# Serial_Card_V3.net
KiCad netlist of a schematic drawn in EAGLE
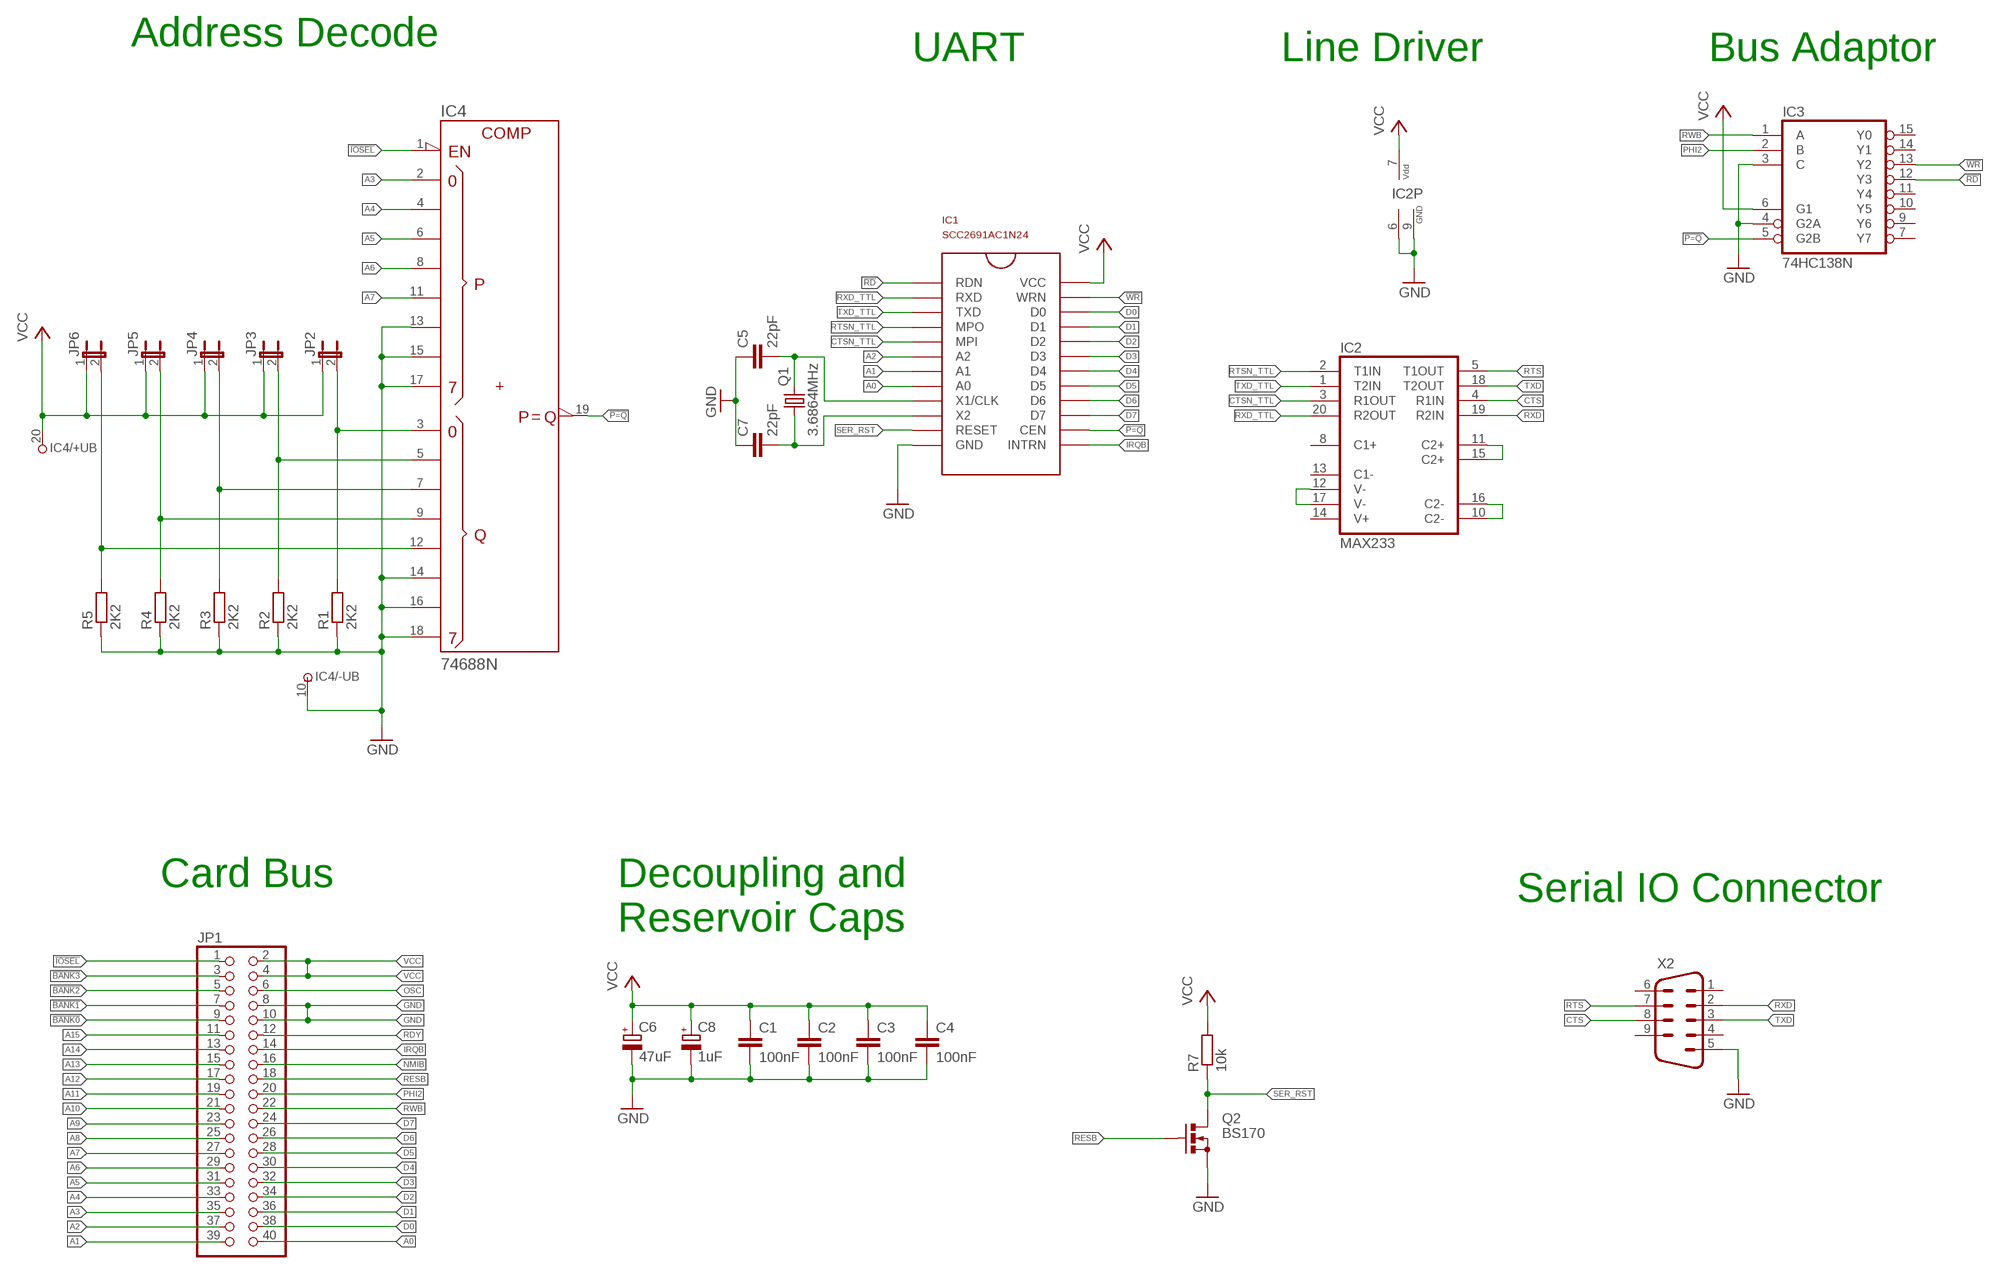
[diagram p0: schematic, sheet 1]

(export (version "E")
  (design (tool "Eeschema 10.0.6"))
  (components
    (comp (ref "C1")
      (value "100nF")
      (footprint "eagle-import:C050-025X075")
      (libsource (lib "eagle-import") (part "C-EU050-025X075"))
    )
    (comp (ref "C2")
      (value "100nF")
      (footprint "eagle-import:C050-025X075")
      (libsource (lib "eagle-import") (part "C-EU050-025X075"))
    )
    (comp (ref "C3")
      (value "100nF")
      (footprint "eagle-import:C050-025X075")
      (libsource (lib "eagle-import") (part "C-EU050-025X075"))
    )
    (comp (ref "C4")
      (value "100nF")
      (footprint "eagle-import:C050-025X075")
      (libsource (lib "eagle-import") (part "C-EU050-025X075"))
    )
    (comp (ref "C5")
      (value "22pF")
      (footprint "eagle-import:C025-024X044")
      (libsource (lib "eagle-import") (part "C-EU025-024X044"))
    )
    (comp (ref "C6")
      (value "47uF")
      (footprint "eagle-import:E2,5-7")
      (libsource (lib "eagle-import") (part "CPOL-EUE2.5-7"))
    )
    (comp (ref "C7")
      (value "22pF")
      (footprint "eagle-import:C025-024X044")
      (libsource (lib "eagle-import") (part "C-EU025-024X044"))
    )
    (comp (ref "C8")
      (value "1uF")
      (footprint "eagle-import:E5-5")
      (libsource (lib "eagle-import") (part "CPOL-EUE5-5"))
    )
    (comp (ref "IC1")
      (value "SCC2691AC1N24")
      (footprint "eagle-import:DIP")
      (libsource (lib "eagle-import") (part "SCC2691AC1N24"))
    )
    (comp (ref "IC2")
      (value "MAX233")
      (footprint "eagle-import:DIL20")
      (libsource (lib "eagle-import") (part "MAX233"))
    )
    (comp (ref "IC3")
      (value "74HC138N")
      (footprint "eagle-import:DIL16")
      (libsource (lib "eagle-import") (part "74138NHC"))
    )
    (comp (ref "IC4")
      (value "74688N")
      (footprint "eagle-import:DIL20")
      (libsource (lib "eagle-import") (part "74688N"))
    )
    (comp (ref "JP1")
      (value "PINHD-2X20/90")
      (footprint "eagle-import:2X20_90")
      (libsource (lib "eagle-import") (part "PINHD-2X20/90"))
    )
    (comp (ref "JP2")
      (value "JP1E")
      (footprint "eagle-import:JP1")
      (libsource (lib "eagle-import") (part "JP1E"))
    )
    (comp (ref "JP3")
      (value "JP1E")
      (footprint "eagle-import:JP1")
      (libsource (lib "eagle-import") (part "JP1E"))
    )
    (comp (ref "JP4")
      (value "JP1E")
      (footprint "eagle-import:JP1")
      (libsource (lib "eagle-import") (part "JP1E"))
    )
    (comp (ref "JP5")
      (value "JP1E")
      (footprint "eagle-import:JP1")
      (libsource (lib "eagle-import") (part "JP1E"))
    )
    (comp (ref "JP6")
      (value "JP1E")
      (footprint "eagle-import:JP1")
      (libsource (lib "eagle-import") (part "JP1E"))
    )
    (comp (ref "Q1")
      (value "3.6864MHz")
      (footprint "eagle-import:HC49_S")
      (libsource (lib "eagle-import") (part "CRYSTALHC49S"))
    )
    (comp (ref "Q2")
      (value "BS170")
      (footprint "eagle-import:SOT54E")
      (libsource (lib "eagle-import") (part "BS170"))
    )
    (comp (ref "R1")
      (value "2K2")
      (footprint "eagle-import:0207_2V")
      (libsource (lib "eagle-import") (part "R-EU_0207/2V"))
    )
    (comp (ref "R2")
      (value "2K2")
      (footprint "eagle-import:0207_2V")
      (libsource (lib "eagle-import") (part "R-EU_0207/2V"))
    )
    (comp (ref "R3")
      (value "2K2")
      (footprint "eagle-import:0207_2V")
      (libsource (lib "eagle-import") (part "R-EU_0207/2V"))
    )
    (comp (ref "R4")
      (value "2K2")
      (footprint "eagle-import:0207_2V")
      (libsource (lib "eagle-import") (part "R-EU_0207/2V"))
    )
    (comp (ref "R5")
      (value "2K2")
      (footprint "eagle-import:0207_2V")
      (libsource (lib "eagle-import") (part "R-EU_0207/2V"))
    )
    (comp (ref "R7")
      (value "10k")
      (footprint "eagle-import:0207_2V")
      (libsource (lib "eagle-import") (part "R-EU_0207/2V"))
    )
    (comp (ref "X2")
      (value "M09HP")
      (footprint "eagle-import:M09HP")
      (libsource (lib "eagle-import") (part "M09HP"))
    )
  )
  (nets
    (net (code "1") (name "/~{BANK0}") (class "Default")
      (node (ref "JP1") (pin "9") (pinfunction "9_9") (pintype "passive"))
    )
    (net (code "2") (name "/~{BANK1}") (class "Default")
      (node (ref "JP1") (pin "7") (pinfunction "7_7") (pintype "passive"))
    )
    (net (code "3") (name "/~{BANK2}") (class "Default")
      (node (ref "JP1") (pin "5") (pinfunction "5_5") (pintype "passive"))
    )
    (net (code "4") (name "/~{BANK3}") (class "Default")
      (node (ref "JP1") (pin "3") (pinfunction "3_3") (pintype "passive"))
    )
    (net (code "5") (name "/~{IOSEL}") (class "Default")
      (node (ref "IC4") (pin "1") (pinfunction "~{G}_1") (pintype "input"))
      (node (ref "JP1") (pin "1") (pinfunction "1_1") (pintype "passive"))
    )
    (net (code "6") (name "/~{P=Q}") (class "Default")
      (node (ref "IC1") (pin "CEN") (pinfunction "CEN_CEN") (pintype "input"))
      (node (ref "IC3") (pin "5") (pinfunction "G2B_5") (pintype "input"))
      (node (ref "IC4") (pin "19") (pinfunction "~{P=Q}_19") (pintype "output"))
    )
    (net (code "7") (name "/~{RD}") (class "Default")
      (node (ref "IC1") (pin "RDN") (pinfunction "RDN_RDN") (pintype "input"))
      (node (ref "IC3") (pin "12") (pinfunction "Y3_12") (pintype "output"))
    )
    (net (code "8") (name "/~{WR}") (class "Default")
      (node (ref "IC1") (pin "WRN") (pinfunction "WRN_WRN") (pintype "bidirectional"))
      (node (ref "IC3") (pin "13") (pinfunction "Y2_13") (pintype "output"))
    )
    (net (code "9") (name "A0") (class "Default")
      (node (ref "IC1") (pin "A0") (pinfunction "A0_A0") (pintype "input"))
      (node (ref "JP1") (pin "40") (pinfunction "40_40") (pintype "passive"))
    )
    (net (code "10") (name "A1") (class "Default")
      (node (ref "IC1") (pin "A1") (pinfunction "A1_A1") (pintype "input"))
      (node (ref "JP1") (pin "39") (pinfunction "39_39") (pintype "passive"))
    )
    (net (code "11") (name "A2") (class "Default")
      (node (ref "IC1") (pin "A2") (pinfunction "A2_A2") (pintype "input"))
      (node (ref "JP1") (pin "37") (pinfunction "37_37") (pintype "passive"))
    )
    (net (code "12") (name "A3") (class "Default")
      (node (ref "IC4") (pin "2") (pinfunction "P0_2") (pintype "input"))
      (node (ref "JP1") (pin "35") (pinfunction "35_35") (pintype "passive"))
    )
    (net (code "13") (name "A4") (class "Default")
      (node (ref "IC4") (pin "4") (pinfunction "P1_4") (pintype "input"))
      (node (ref "JP1") (pin "33") (pinfunction "33_33") (pintype "passive"))
    )
    (net (code "14") (name "A5") (class "Default")
      (node (ref "IC4") (pin "6") (pinfunction "P2_6") (pintype "input"))
      (node (ref "JP1") (pin "31") (pinfunction "31_31") (pintype "passive"))
    )
    (net (code "15") (name "A6") (class "Default")
      (node (ref "IC4") (pin "8") (pinfunction "P3_8") (pintype "input"))
      (node (ref "JP1") (pin "29") (pinfunction "29_29") (pintype "passive"))
    )
    (net (code "16") (name "A7") (class "Default")
      (node (ref "IC4") (pin "11") (pinfunction "P4_11") (pintype "input"))
      (node (ref "JP1") (pin "27") (pinfunction "27_27") (pintype "passive"))
    )
    (net (code "17") (name "A8") (class "Default")
      (node (ref "JP1") (pin "25") (pinfunction "25_25") (pintype "passive"))
    )
    (net (code "18") (name "A9") (class "Default")
      (node (ref "JP1") (pin "23") (pinfunction "23_23") (pintype "passive"))
    )
    (net (code "19") (name "A10") (class "Default")
      (node (ref "JP1") (pin "21") (pinfunction "21_21") (pintype "passive"))
    )
    (net (code "20") (name "A11") (class "Default")
      (node (ref "JP1") (pin "19") (pinfunction "19_19") (pintype "passive"))
    )
    (net (code "21") (name "A12") (class "Default")
      (node (ref "JP1") (pin "17") (pinfunction "17_17") (pintype "passive"))
    )
    (net (code "22") (name "A13") (class "Default")
      (node (ref "JP1") (pin "15") (pinfunction "15_15") (pintype "passive"))
    )
    (net (code "23") (name "A14") (class "Default")
      (node (ref "JP1") (pin "13") (pinfunction "13_13") (pintype "passive"))
    )
    (net (code "24") (name "A15") (class "Default")
      (node (ref "JP1") (pin "11") (pinfunction "11_11") (pintype "passive"))
    )
    (net (code "25") (name "CTS") (class "Default")
      (node (ref "IC2") (pin "4") (pinfunction "R1IN_4") (pintype "input"))
      (node (ref "X2") (pin "8") (pinfunction "8_8") (pintype "passive"))
    )
    (net (code "26") (name "CTSN_TTL") (class "Default")
      (node (ref "IC1") (pin "MPI") (pinfunction "MPI_MPI") (pintype "input"))
      (node (ref "IC2") (pin "3") (pinfunction "R1OUT_3") (pintype "output"))
    )
    (net (code "27") (name "D0") (class "Default")
      (node (ref "IC1") (pin "D0") (pinfunction "D0_D0") (pintype "bidirectional"))
      (node (ref "JP1") (pin "38") (pinfunction "38_38") (pintype "passive"))
    )
    (net (code "28") (name "D1") (class "Default")
      (node (ref "IC1") (pin "D1") (pinfunction "D1_D1") (pintype "bidirectional"))
      (node (ref "JP1") (pin "36") (pinfunction "36_36") (pintype "passive"))
    )
    (net (code "29") (name "D2") (class "Default")
      (node (ref "IC1") (pin "D2") (pinfunction "D2_D2") (pintype "bidirectional"))
      (node (ref "JP1") (pin "34") (pinfunction "34_34") (pintype "passive"))
    )
    (net (code "30") (name "D3") (class "Default")
      (node (ref "IC1") (pin "D3") (pinfunction "D3_D3") (pintype "bidirectional"))
      (node (ref "JP1") (pin "32") (pinfunction "32_32") (pintype "passive"))
    )
    (net (code "31") (name "D4") (class "Default")
      (node (ref "IC1") (pin "D4") (pinfunction "D4_D4") (pintype "bidirectional"))
      (node (ref "JP1") (pin "30") (pinfunction "30_30") (pintype "passive"))
    )
    (net (code "32") (name "D5") (class "Default")
      (node (ref "IC1") (pin "D5") (pinfunction "D5_D5") (pintype "bidirectional"))
      (node (ref "JP1") (pin "28") (pinfunction "28_28") (pintype "passive"))
    )
    (net (code "33") (name "D6") (class "Default")
      (node (ref "IC1") (pin "D6") (pinfunction "D6_D6") (pintype "bidirectional"))
      (node (ref "JP1") (pin "26") (pinfunction "26_26") (pintype "passive"))
    )
    (net (code "34") (name "D7") (class "Default")
      (node (ref "IC1") (pin "D7") (pinfunction "D7_D7") (pintype "bidirectional"))
      (node (ref "JP1") (pin "24") (pinfunction "24_24") (pintype "passive"))
    )
    (net (code "35") (name "GND") (class "Default")
      (node (ref "C1") (pin "2") (pinfunction "2_2") (pintype "passive"))
      (node (ref "C2") (pin "2") (pinfunction "2_2") (pintype "passive"))
      (node (ref "C3") (pin "2") (pinfunction "2_2") (pintype "passive"))
      (node (ref "C4") (pin "2") (pinfunction "2_2") (pintype "passive"))
      (node (ref "C5") (pin "1") (pinfunction "1_1") (pintype "passive"))
      (node (ref "C6") (pin "-") (pinfunction "-_-") (pintype "passive"))
      (node (ref "C7") (pin "1") (pinfunction "1_1") (pintype "passive"))
      (node (ref "C8") (pin "-") (pinfunction "-_-") (pintype "passive"))
      (node (ref "IC1") (pin "GND") (pinfunction "GND_GND") (pintype "power_in"))
      (node (ref "IC2") (pin "6") (pinfunction "GND_6") (pintype "power_in"))
      (node (ref "IC2") (pin "9") (pinfunction "GND_9") (pintype "power_in"))
      (node (ref "IC3") (pin "3") (pinfunction "C_3") (pintype "input"))
      (node (ref "IC3") (pin "4") (pinfunction "G2A_4") (pintype "input"))
      (node (ref "IC4") (pin "10") (pinfunction "-UB_10") (pintype "power_in"))
      (node (ref "IC4") (pin "13") (pinfunction "P5_13") (pintype "input"))
      (node (ref "IC4") (pin "14") (pinfunction "Q5_14") (pintype "input"))
      (node (ref "IC4") (pin "15") (pinfunction "P6_15") (pintype "input"))
      (node (ref "IC4") (pin "16") (pinfunction "Q6_16") (pintype "input"))
      (node (ref "IC4") (pin "17") (pinfunction "P7_17") (pintype "input"))
      (node (ref "IC4") (pin "18") (pinfunction "Q7_18") (pintype "input"))
      (node (ref "JP1") (pin "10") (pinfunction "10_10") (pintype "passive"))
      (node (ref "JP1") (pin "8") (pinfunction "8_8") (pintype "passive"))
      (node (ref "Q2") (pin "S") (pinfunction "S_S") (pintype "passive"))
      (node (ref "R1") (pin "1") (pinfunction "1_1") (pintype "passive"))
      (node (ref "R2") (pin "1") (pinfunction "1_1") (pintype "passive"))
      (node (ref "R3") (pin "1") (pinfunction "1_1") (pintype "passive"))
      (node (ref "R4") (pin "1") (pinfunction "1_1") (pintype "passive"))
      (node (ref "R5") (pin "1") (pinfunction "1_1") (pintype "passive"))
      (node (ref "X2") (pin "5") (pinfunction "5_5") (pintype "passive"))
    )
    (net (code "36") (name "IRQB") (class "Default")
      (node (ref "IC1") (pin "INTRN") (pinfunction "INTRN_INTRN") (pintype "output"))
      (node (ref "JP1") (pin "14") (pinfunction "14_14") (pintype "passive"))
    )
    (net (code "37") (name "NMIB") (class "Default")
      (node (ref "JP1") (pin "16") (pinfunction "16_16") (pintype "passive"))
    )
    (net (code "38") (name "Net-(C5-Pad2)") (class "Default")
      (node (ref "C5") (pin "2") (pinfunction "2_2") (pintype "passive"))
      (node (ref "IC1") (pin "X1/CLK") (pinfunction "X1/CLK_X1/CLK") (pintype "input"))
      (node (ref "Q1") (pin "2") (pinfunction "2_2") (pintype "passive"))
    )
    (net (code "39") (name "Net-(C7-Pad2)") (class "Default")
      (node (ref "C7") (pin "2") (pinfunction "2_2") (pintype "passive"))
      (node (ref "IC1") (pin "X2") (pinfunction "X2_X2") (pintype "output"))
      (node (ref "Q1") (pin "1") (pinfunction "1_1") (pintype "passive"))
    )
    (net (code "40") (name "Net-(IC2A-C2+-Pad11)") (class "Default")
      (node (ref "IC2") (pin "11") (pinfunction "C2+_11") (pintype "bidirectional"))
      (node (ref "IC2") (pin "15") (pinfunction "C2+_15") (pintype "bidirectional"))
    )
    (net (code "41") (name "Net-(IC2A-C2--Pad10)") (class "Default")
      (node (ref "IC2") (pin "10") (pinfunction "C2-_10") (pintype "bidirectional"))
      (node (ref "IC2") (pin "16") (pinfunction "C2-_16") (pintype "bidirectional"))
    )
    (net (code "42") (name "Net-(IC2A-V--Pad12)") (class "Default")
      (node (ref "IC2") (pin "12") (pinfunction "V-_12") (pintype "bidirectional"))
      (node (ref "IC2") (pin "17") (pinfunction "V-_17") (pintype "bidirectional"))
    )
    (net (code "43") (name "Net-(IC4C-Q0)") (class "Default")
      (node (ref "IC4") (pin "3") (pinfunction "Q0_3") (pintype "input"))
      (node (ref "JP2") (pin "2") (pinfunction "2_2") (pintype "passive"))
      (node (ref "R1") (pin "2") (pinfunction "2_2") (pintype "passive"))
    )
    (net (code "44") (name "Net-(IC4C-Q1)") (class "Default")
      (node (ref "IC4") (pin "5") (pinfunction "Q1_5") (pintype "input"))
      (node (ref "JP3") (pin "2") (pinfunction "2_2") (pintype "passive"))
      (node (ref "R2") (pin "2") (pinfunction "2_2") (pintype "passive"))
    )
    (net (code "45") (name "Net-(IC4C-Q2)") (class "Default")
      (node (ref "IC4") (pin "7") (pinfunction "Q2_7") (pintype "input"))
      (node (ref "JP4") (pin "2") (pinfunction "2_2") (pintype "passive"))
      (node (ref "R3") (pin "2") (pinfunction "2_2") (pintype "passive"))
    )
    (net (code "46") (name "Net-(IC4C-Q3)") (class "Default")
      (node (ref "IC4") (pin "9") (pinfunction "Q3_9") (pintype "input"))
      (node (ref "JP5") (pin "2") (pinfunction "2_2") (pintype "passive"))
      (node (ref "R4") (pin "2") (pinfunction "2_2") (pintype "passive"))
    )
    (net (code "47") (name "Net-(IC4C-Q4)") (class "Default")
      (node (ref "IC4") (pin "12") (pinfunction "Q4_12") (pintype "input"))
      (node (ref "JP6") (pin "2") (pinfunction "2_2") (pintype "passive"))
      (node (ref "R5") (pin "2") (pinfunction "2_2") (pintype "passive"))
    )
    (net (code "48") (name "OSC") (class "Default")
      (node (ref "JP1") (pin "6") (pinfunction "6_6") (pintype "passive"))
    )
    (net (code "49") (name "PHI2") (class "Default")
      (node (ref "IC3") (pin "2") (pinfunction "B_2") (pintype "input"))
      (node (ref "JP1") (pin "20") (pinfunction "20_20") (pintype "passive"))
    )
    (net (code "50") (name "RDY") (class "Default")
      (node (ref "JP1") (pin "12") (pinfunction "12_12") (pintype "passive"))
    )
    (net (code "51") (name "RESB") (class "Default")
      (node (ref "JP1") (pin "18") (pinfunction "18_18") (pintype "passive"))
      (node (ref "Q2") (pin "G") (pinfunction "G_G") (pintype "passive"))
    )
    (net (code "52") (name "RTS") (class "Default")
      (node (ref "IC2") (pin "5") (pinfunction "T1OUT_5") (pintype "output"))
      (node (ref "X2") (pin "7") (pinfunction "7_7") (pintype "passive"))
    )
    (net (code "53") (name "RTSN_TTL") (class "Default")
      (node (ref "IC1") (pin "MPO") (pinfunction "MPO_MPO") (pintype "output"))
      (node (ref "IC2") (pin "2") (pinfunction "T1IN_2") (pintype "input"))
    )
    (net (code "54") (name "RWB") (class "Default")
      (node (ref "IC3") (pin "1") (pinfunction "A_1") (pintype "input"))
      (node (ref "JP1") (pin "22") (pinfunction "22_22") (pintype "passive"))
    )
    (net (code "55") (name "RXD") (class "Default")
      (node (ref "IC2") (pin "19") (pinfunction "R2IN_19") (pintype "input"))
      (node (ref "X2") (pin "2") (pinfunction "2_2") (pintype "passive"))
    )
    (net (code "56") (name "RXD_TTL") (class "Default")
      (node (ref "IC1") (pin "RXD") (pinfunction "RXD_RXD") (pintype "input"))
      (node (ref "IC2") (pin "20") (pinfunction "R2OUT_20") (pintype "output"))
    )
    (net (code "57") (name "SER_RST") (class "Default")
      (node (ref "IC1") (pin "RESET") (pinfunction "RESET_RESET") (pintype "input"))
      (node (ref "Q2") (pin "D") (pinfunction "D_D") (pintype "passive"))
      (node (ref "R7") (pin "1") (pinfunction "1_1") (pintype "passive"))
    )
    (net (code "58") (name "TXD") (class "Default")
      (node (ref "IC2") (pin "18") (pinfunction "T2OUT_18") (pintype "output"))
      (node (ref "X2") (pin "3") (pinfunction "3_3") (pintype "passive"))
    )
    (net (code "59") (name "TXD_TTL") (class "Default")
      (node (ref "IC1") (pin "TXD") (pinfunction "TXD_TXD") (pintype "output"))
      (node (ref "IC2") (pin "1") (pinfunction "T2IN_1") (pintype "input"))
    )
    (net (code "60") (name "VCC") (class "Default")
      (node (ref "C1") (pin "1") (pinfunction "1_1") (pintype "passive"))
      (node (ref "C2") (pin "1") (pinfunction "1_1") (pintype "passive"))
      (node (ref "C3") (pin "1") (pinfunction "1_1") (pintype "passive"))
      (node (ref "C4") (pin "1") (pinfunction "1_1") (pintype "passive"))
      (node (ref "C6") (pin "+") (pinfunction "+_+") (pintype "passive"))
      (node (ref "C8") (pin "+") (pinfunction "+_+") (pintype "passive"))
      (node (ref "IC1") (pin "VCC") (pinfunction "VCC_VCC") (pintype "power_in"))
      (node (ref "IC2") (pin "7") (pinfunction "VDD_7") (pintype "power_in"))
      (node (ref "IC3") (pin "6") (pinfunction "G1_6") (pintype "input"))
      (node (ref "IC4") (pin "20") (pinfunction "+UB_20") (pintype "power_in"))
      (node (ref "JP1") (pin "2") (pinfunction "2_2") (pintype "passive"))
      (node (ref "JP1") (pin "4") (pinfunction "4_4") (pintype "passive"))
      (node (ref "JP2") (pin "1") (pinfunction "1_1") (pintype "passive"))
      (node (ref "JP3") (pin "1") (pinfunction "1_1") (pintype "passive"))
      (node (ref "JP4") (pin "1") (pinfunction "1_1") (pintype "passive"))
      (node (ref "JP5") (pin "1") (pinfunction "1_1") (pintype "passive"))
      (node (ref "JP6") (pin "1") (pinfunction "1_1") (pintype "passive"))
      (node (ref "R7") (pin "2") (pinfunction "2_2") (pintype "passive"))
    )
    (net (code "61") (name "unconnected-(IC2A-C1+-Pad8)") (class "Default")
      (node (ref "IC2") (pin "8") (pinfunction "C1+_8") (pintype "bidirectional"))
    )
    (net (code "62") (name "unconnected-(IC2A-C1--Pad13)") (class "Default")
      (node (ref "IC2") (pin "13") (pinfunction "C1-_13") (pintype "bidirectional"))
    )
    (net (code "63") (name "unconnected-(IC2A-V+-Pad14)") (class "Default")
      (node (ref "IC2") (pin "14") (pinfunction "V+_14") (pintype "bidirectional"))
    )
    (net (code "64") (name "unconnected-(IC3A-Y0-Pad15)") (class "Default")
      (node (ref "IC3") (pin "15") (pinfunction "Y0_15") (pintype "output"))
    )
    (net (code "65") (name "unconnected-(IC3A-Y1-Pad14)") (class "Default")
      (node (ref "IC3") (pin "14") (pinfunction "Y1_14") (pintype "output"))
    )
    (net (code "66") (name "unconnected-(IC3A-Y4-Pad11)") (class "Default")
      (node (ref "IC3") (pin "11") (pinfunction "Y4_11") (pintype "output"))
    )
    (net (code "67") (name "unconnected-(IC3A-Y5-Pad10)") (class "Default")
      (node (ref "IC3") (pin "10") (pinfunction "Y5_10") (pintype "output"))
    )
    (net (code "68") (name "unconnected-(IC3A-Y6-Pad9)") (class "Default")
      (node (ref "IC3") (pin "9") (pinfunction "Y6_9") (pintype "output"))
    )
    (net (code "69") (name "unconnected-(IC3A-Y7-Pad7)") (class "Default")
      (node (ref "IC3") (pin "7") (pinfunction "Y7_7") (pintype "output"))
    )
    (net (code "70") (name "unconnected-(X2-Pad1)") (class "Default")
      (node (ref "X2") (pin "1") (pinfunction "1_1") (pintype "passive"))
    )
    (net (code "71") (name "unconnected-(X2-Pad4)") (class "Default")
      (node (ref "X2") (pin "4") (pinfunction "4_4") (pintype "passive"))
    )
    (net (code "72") (name "unconnected-(X2-Pad6)") (class "Default")
      (node (ref "X2") (pin "6") (pinfunction "6_6") (pintype "passive"))
    )
    (net (code "73") (name "unconnected-(X2-Pad9)") (class "Default")
      (node (ref "X2") (pin "9") (pinfunction "9_9") (pintype "passive"))
    )
  )
)
